# SampleHoldCircuit.net
KiCad netlist of a schematic drawn in Altium Designer
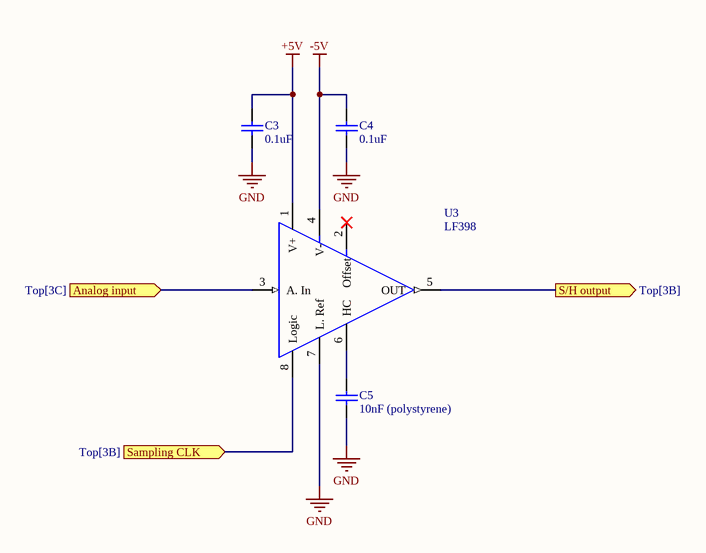
[diagram p0: SampleHoldCircuit.SchDoc]

(export (version "E")
  (design (tool "Eeschema 10.0.6"))
  (components
    (comp (ref "C3")
      (value "0.1uF")
      (description "Ceramic Capacitor")
      (fields (field (name "PUBLISHER") "Altium Limited"))
      (libsource (lib "ECET231SCHLIB_Rev01") (part "Cap"))
    )
    (comp (ref "C4")
      (value "0.1uF")
      (description "Ceramic Capacitor")
      (fields (field (name "PUBLISHER") "Altium Limited"))
      (libsource (lib "ECET231SCHLIB_Rev01") (part "Cap"))
    )
    (comp (ref "C5")
      (value "10nF (polystyrene)")
      (description "Ceramic Capacitor")
      (fields (field (name "PUBLISHER") "Altium Limited"))
      (libsource (lib "ECET231SCHLIB_Rev01") (part "Cap"))
    )
    (comp (ref "U3")
      (value "LF398")
      (description "Sample and Hold")
      (libsource (lib "ECET231SCHLIB_Rev01") (part "LF398"))
    )
  )
  (nets
    (net (code "1") (name "+5V") (class "Default")
      (node (ref "C3") (pin "2") (pinfunction "2_2") (pintype "passive"))
      (node (ref "U3") (pin "1") (pinfunction "V+_1") (pintype "power_in"))
    )
    (net (code "2") (name "-5V") (class "Default")
      (node (ref "C4") (pin "2") (pinfunction "2_2") (pintype "passive"))
      (node (ref "U3") (pin "4") (pinfunction "V-_4") (pintype "power_in"))
    )
    (net (code "3") (name "/Analog input") (class "Default")
      (node (ref "U3") (pin "3") (pinfunction "A._In_3") (pintype "input"))
    )
    (net (code "4") (name "/Sampling CLK") (class "Default")
      (node (ref "U3") (pin "8") (pinfunction "Logic_8") (pintype "passive"))
    )
    (net (code "5") (name "/S{slash}H output") (class "Default")
      (node (ref "U3") (pin "5") (pinfunction "OUT_5") (pintype "output"))
    )
    (net (code "6") (name "GND") (class "Default")
      (node (ref "C3") (pin "1") (pinfunction "1_1") (pintype "passive"))
      (node (ref "C4") (pin "1") (pinfunction "1_1") (pintype "passive"))
      (node (ref "C5") (pin "1") (pinfunction "1_1") (pintype "passive"))
      (node (ref "U3") (pin "7") (pinfunction "L._Ref_7") (pintype "passive"))
    )
    (net (code "7") (name "Net-(U3-HC)") (class "Default")
      (node (ref "C5") (pin "2") (pinfunction "2_2") (pintype "passive"))
      (node (ref "U3") (pin "6") (pinfunction "HC_6") (pintype "passive"))
    )
    (net (code "8") (name "unconnected-(U3-Offset-Pad2)") (class "Default")
      (node (ref "U3") (pin "2") (pinfunction "Offset_2") (pintype "passive+no_connect"))
    )
  )
)
